# LPC1114_LedMatrix.net
KiCad netlist of a schematic drawn in EAGLE
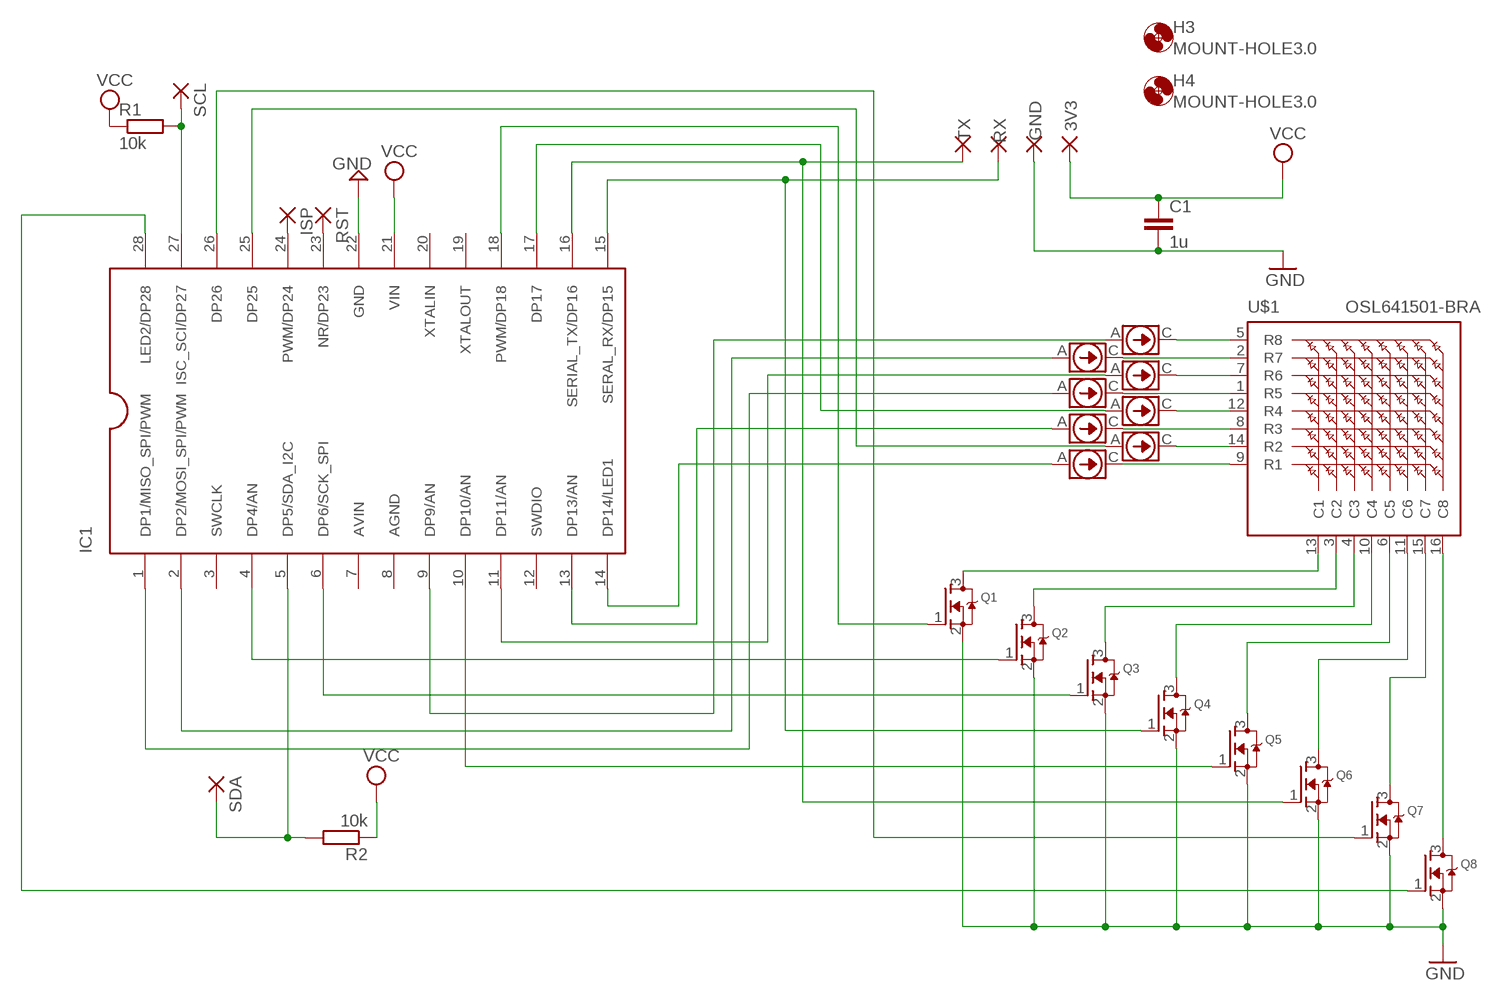
[diagram p0: schematic, sheet 1]

(export (version "E")
  (design (tool "Eeschema 10.0.6"))
  (components
    (comp (ref "3V3")
      (value "1,6/0,8")
      (footprint "eagle-import:1,6_0,8")
      (libsource (lib "eagle-import") (part "1,6/0,8"))
    )
    (comp (ref "C1")
      (value "1u")
      (footprint "eagle-import:C0603")
      (libsource (lib "eagle-import") (part "C-EUC0603"))
    )
    (comp (ref "CRD1")
      (value "NSI45020AT1G")
      (footprint "eagle-import:SOD-123")
      (libsource (lib "eagle-import") (part "NSI45020AT1G"))
    )
    (comp (ref "CRD2")
      (value "NSI45020AT1G")
      (footprint "eagle-import:SOD-123")
      (libsource (lib "eagle-import") (part "NSI45020AT1G"))
    )
    (comp (ref "CRD3")
      (value "NSI45020AT1G")
      (footprint "eagle-import:SOD-123")
      (libsource (lib "eagle-import") (part "NSI45020AT1G"))
    )
    (comp (ref "CRD4")
      (value "NSI45020AT1G")
      (footprint "eagle-import:SOD-123")
      (libsource (lib "eagle-import") (part "NSI45020AT1G"))
    )
    (comp (ref "CRD5")
      (value "NSI45020AT1G")
      (footprint "eagle-import:SOD-123")
      (libsource (lib "eagle-import") (part "NSI45020AT1G"))
    )
    (comp (ref "CRD6")
      (value "NSI45020AT1G")
      (footprint "eagle-import:SOD-123")
      (libsource (lib "eagle-import") (part "NSI45020AT1G"))
    )
    (comp (ref "CRD7")
      (value "NSI45020AT1G")
      (footprint "eagle-import:SOD-123")
      (libsource (lib "eagle-import") (part "NSI45020AT1G"))
    )
    (comp (ref "CRD8")
      (value "NSI45020AT1G")
      (footprint "eagle-import:SOD-123")
      (libsource (lib "eagle-import") (part "NSI45020AT1G"))
    )
    (comp (ref "GND")
      (value "1,6/0,8")
      (footprint "eagle-import:1,6_0,8")
      (libsource (lib "eagle-import") (part "1,6/0,8"))
    )
    (comp (ref "H3")
      (value "MOUNT-HOLE3.0")
      (footprint "eagle-import:3,0")
      (libsource (lib "eagle-import") (part "MOUNT-HOLE3.0"))
    )
    (comp (ref "H4")
      (value "MOUNT-HOLE3.0")
      (footprint "eagle-import:3,0")
      (libsource (lib "eagle-import") (part "MOUNT-HOLE3.0"))
    )
    (comp (ref "IC1")
      (value "LPC1114FN28")
      (footprint "eagle-import:DIP28")
      (libsource (lib "eagle-import") (part "LPC1114FN28"))
    )
    (comp (ref "ISP")
      (value "1,6/0,8")
      (footprint "eagle-import:1,6_0,8")
      (libsource (lib "eagle-import") (part "1,6/0,8"))
    )
    (comp (ref "Q1")
      (value "MOSFET-NREFLOW")
      (footprint "eagle-import:SOT23")
      (libsource (lib "eagle-import") (part "MOSFET-NREFLOW"))
    )
    (comp (ref "Q2")
      (value "MOSFET-NREFLOW")
      (footprint "eagle-import:SOT23")
      (libsource (lib "eagle-import") (part "MOSFET-NREFLOW"))
    )
    (comp (ref "Q3")
      (value "MOSFET-NREFLOW")
      (footprint "eagle-import:SOT23")
      (libsource (lib "eagle-import") (part "MOSFET-NREFLOW"))
    )
    (comp (ref "Q4")
      (value "MOSFET-NREFLOW")
      (footprint "eagle-import:SOT23")
      (libsource (lib "eagle-import") (part "MOSFET-NREFLOW"))
    )
    (comp (ref "Q5")
      (value "MOSFET-NREFLOW")
      (footprint "eagle-import:SOT23")
      (libsource (lib "eagle-import") (part "MOSFET-NREFLOW"))
    )
    (comp (ref "Q6")
      (value "MOSFET-NREFLOW")
      (footprint "eagle-import:SOT23")
      (libsource (lib "eagle-import") (part "MOSFET-NREFLOW"))
    )
    (comp (ref "Q7")
      (value "MOSFET-NREFLOW")
      (footprint "eagle-import:SOT23")
      (libsource (lib "eagle-import") (part "MOSFET-NREFLOW"))
    )
    (comp (ref "Q8")
      (value "MOSFET-NREFLOW")
      (footprint "eagle-import:SOT23")
      (libsource (lib "eagle-import") (part "MOSFET-NREFLOW"))
    )
    (comp (ref "R1")
      (value "10k")
      (footprint "eagle-import:R0603")
      (libsource (lib "eagle-import") (part "R-EU_R0603"))
    )
    (comp (ref "R2")
      (value "10k")
      (footprint "eagle-import:R0603")
      (libsource (lib "eagle-import") (part "R-EU_R0603"))
    )
    (comp (ref "RST")
      (value "1,6/0,8")
      (footprint "eagle-import:1,6_0,8")
      (libsource (lib "eagle-import") (part "1,6/0,8"))
    )
    (comp (ref "RX")
      (value "1,6/0,8")
      (footprint "eagle-import:1,6_0,8")
      (libsource (lib "eagle-import") (part "1,6/0,8"))
    )
    (comp (ref "SCL")
      (value "1,6/0,8")
      (footprint "eagle-import:1,6_0,8")
      (libsource (lib "eagle-import") (part "1,6/0,8"))
    )
    (comp (ref "SDA")
      (value "1,6/0,8")
      (footprint "eagle-import:1,6_0,8")
      (libsource (lib "eagle-import") (part "1,6/0,8"))
    )
    (comp (ref "TX")
      (value "1,6/0,8")
      (footprint "eagle-import:1,6_0,8")
      (libsource (lib "eagle-import") (part "1,6/0,8"))
    )
    (comp (ref "U$1")
      (value "OSL641501-BRA")
      (footprint "eagle-import:OSL641501")
      (libsource (lib "eagle-import") (part "OSL641501-BRA"))
    )
  )
  (nets
    (net (code "1") (name "/AGND") (class "Default")
      (node (ref "IC1") (pin "8") (pinfunction "AGND_8") (pintype "power_in"))
    )
    (net (code "2") (name "/AVIN") (class "Default")
      (node (ref "IC1") (pin "7") (pinfunction "AVIN_7") (pintype "power_in"))
    )
    (net (code "3") (name "GND") (class "Default")
      (node (ref "C1") (pin "2") (pinfunction "2_2") (pintype "passive"))
      (node (ref "GND") (pin "1") (pinfunction "P_1") (pintype "passive"))
      (node (ref "IC1") (pin "22") (pinfunction "GND_22") (pintype "power_in"))
      (node (ref "Q1") (pin "2") (pinfunction "S_2") (pintype "bidirectional"))
      (node (ref "Q2") (pin "2") (pinfunction "S_2") (pintype "bidirectional"))
      (node (ref "Q3") (pin "2") (pinfunction "S_2") (pintype "bidirectional"))
      (node (ref "Q4") (pin "2") (pinfunction "S_2") (pintype "bidirectional"))
      (node (ref "Q5") (pin "2") (pinfunction "S_2") (pintype "bidirectional"))
      (node (ref "Q6") (pin "2") (pinfunction "S_2") (pintype "bidirectional"))
      (node (ref "Q7") (pin "2") (pinfunction "S_2") (pintype "bidirectional"))
      (node (ref "Q8") (pin "2") (pinfunction "S_2") (pintype "bidirectional"))
    )
    (net (code "4") (name "Net-(CRD1-P$1)") (class "Default")
      (node (ref "CRD1") (pin "A") (pinfunction "P$1_A") (pintype "input"))
      (node (ref "IC1") (pin "14") (pinfunction "DP14/LED1_14") (pintype "bidirectional"))
    )
    (net (code "5") (name "Net-(CRD1-P$2)") (class "Default")
      (node (ref "CRD1") (pin "C") (pinfunction "P$2_C") (pintype "output"))
      (node (ref "U$1") (pin "9") (pinfunction "R1_9") (pintype "passive"))
    )
    (net (code "6") (name "Net-(CRD2-P$1)") (class "Default")
      (node (ref "CRD2") (pin "A") (pinfunction "P$1_A") (pintype "input"))
      (node (ref "IC1") (pin "25") (pinfunction "DP25_25") (pintype "bidirectional"))
    )
    (net (code "7") (name "Net-(CRD2-P$2)") (class "Default")
      (node (ref "CRD2") (pin "C") (pinfunction "P$2_C") (pintype "output"))
      (node (ref "U$1") (pin "14") (pinfunction "R2_14") (pintype "passive"))
    )
    (net (code "8") (name "Net-(CRD3-P$1)") (class "Default")
      (node (ref "CRD3") (pin "A") (pinfunction "P$1_A") (pintype "input"))
      (node (ref "IC1") (pin "13") (pinfunction "DP13/AN_13") (pintype "bidirectional"))
    )
    (net (code "9") (name "Net-(CRD3-P$2)") (class "Default")
      (node (ref "CRD3") (pin "C") (pinfunction "P$2_C") (pintype "output"))
      (node (ref "U$1") (pin "8") (pinfunction "R3_8") (pintype "passive"))
    )
    (net (code "10") (name "Net-(CRD4-P$1)") (class "Default")
      (node (ref "CRD4") (pin "A") (pinfunction "P$1_A") (pintype "input"))
      (node (ref "IC1") (pin "17") (pinfunction "DP17_17") (pintype "bidirectional"))
    )
    (net (code "11") (name "Net-(CRD4-P$2)") (class "Default")
      (node (ref "CRD4") (pin "C") (pinfunction "P$2_C") (pintype "output"))
      (node (ref "U$1") (pin "12") (pinfunction "R4_12") (pintype "passive"))
    )
    (net (code "12") (name "Net-(CRD5-P$1)") (class "Default")
      (node (ref "CRD5") (pin "A") (pinfunction "P$1_A") (pintype "input"))
      (node (ref "IC1") (pin "1") (pinfunction "DP1/MISO_SPI/PWM_1") (pintype "bidirectional"))
    )
    (net (code "13") (name "Net-(CRD5-P$2)") (class "Default")
      (node (ref "CRD5") (pin "C") (pinfunction "P$2_C") (pintype "output"))
      (node (ref "U$1") (pin "1") (pinfunction "R5_1") (pintype "passive"))
    )
    (net (code "14") (name "Net-(CRD6-P$1)") (class "Default")
      (node (ref "CRD6") (pin "A") (pinfunction "P$1_A") (pintype "input"))
      (node (ref "IC1") (pin "11") (pinfunction "DP11/AN_11") (pintype "bidirectional"))
    )
    (net (code "15") (name "Net-(CRD6-P$2)") (class "Default")
      (node (ref "CRD6") (pin "C") (pinfunction "P$2_C") (pintype "output"))
      (node (ref "U$1") (pin "7") (pinfunction "R6_7") (pintype "passive"))
    )
    (net (code "16") (name "Net-(CRD7-P$1)") (class "Default")
      (node (ref "CRD7") (pin "A") (pinfunction "P$1_A") (pintype "input"))
      (node (ref "IC1") (pin "2") (pinfunction "DP2/MOSI_SPI/PWM_2") (pintype "bidirectional"))
    )
    (net (code "17") (name "Net-(CRD7-P$2)") (class "Default")
      (node (ref "CRD7") (pin "C") (pinfunction "P$2_C") (pintype "output"))
      (node (ref "U$1") (pin "2") (pinfunction "R7_2") (pintype "passive"))
    )
    (net (code "18") (name "Net-(CRD8-P$1)") (class "Default")
      (node (ref "CRD8") (pin "A") (pinfunction "P$1_A") (pintype "input"))
      (node (ref "IC1") (pin "9") (pinfunction "DP9/AN_9") (pintype "bidirectional"))
    )
    (net (code "19") (name "Net-(CRD8-P$2)") (class "Default")
      (node (ref "CRD8") (pin "C") (pinfunction "P$2_C") (pintype "output"))
      (node (ref "U$1") (pin "5") (pinfunction "R8_5") (pintype "passive"))
    )
    (net (code "20") (name "Net-(IC1-DP4{slash}AN)") (class "Default")
      (node (ref "IC1") (pin "4") (pinfunction "DP4/AN_4") (pintype "bidirectional"))
      (node (ref "Q2") (pin "1") (pinfunction "G_1") (pintype "bidirectional"))
    )
    (net (code "21") (name "Net-(IC1-DP5{slash}SDA_I2C)") (class "Default")
      (node (ref "IC1") (pin "5") (pinfunction "DP5/SDA_I2C_5") (pintype "bidirectional"))
      (node (ref "R2") (pin "2") (pinfunction "2_2") (pintype "passive"))
      (node (ref "SDA") (pin "1") (pinfunction "P_1") (pintype "passive"))
    )
    (net (code "22") (name "Net-(IC1-DP6{slash}SCK_SPI)") (class "Default")
      (node (ref "IC1") (pin "6") (pinfunction "DP6/SCK_SPI_6") (pintype "bidirectional"))
      (node (ref "Q3") (pin "1") (pinfunction "G_1") (pintype "bidirectional"))
    )
    (net (code "23") (name "Net-(IC1-DP10{slash}AN)") (class "Default")
      (node (ref "IC1") (pin "10") (pinfunction "DP10/AN_10") (pintype "bidirectional"))
      (node (ref "Q5") (pin "1") (pinfunction "G_1") (pintype "bidirectional"))
    )
    (net (code "24") (name "Net-(IC1-DP26)") (class "Default")
      (node (ref "IC1") (pin "26") (pinfunction "DP26_26") (pintype "bidirectional"))
      (node (ref "Q7") (pin "1") (pinfunction "G_1") (pintype "bidirectional"))
    )
    (net (code "25") (name "Net-(IC1-ISC_SCI{slash}DP27)") (class "Default")
      (node (ref "IC1") (pin "27") (pinfunction "ISC_SCI/DP27_27") (pintype "bidirectional"))
      (node (ref "R1") (pin "2") (pinfunction "2_2") (pintype "passive"))
      (node (ref "SCL") (pin "1") (pinfunction "P_1") (pintype "passive"))
    )
    (net (code "26") (name "Net-(IC1-LED2{slash}DP28)") (class "Default")
      (node (ref "IC1") (pin "28") (pinfunction "LED2/DP28_28") (pintype "bidirectional"))
      (node (ref "Q8") (pin "1") (pinfunction "G_1") (pintype "bidirectional"))
    )
    (net (code "27") (name "Net-(IC1-NR{slash}DP23)") (class "Default")
      (node (ref "IC1") (pin "23") (pinfunction "NR/DP23_23") (pintype "bidirectional"))
      (node (ref "RST") (pin "1") (pinfunction "P_1") (pintype "passive"))
    )
    (net (code "28") (name "Net-(IC1-PWM{slash}DP18)") (class "Default")
      (node (ref "IC1") (pin "18") (pinfunction "PWM/DP18_18") (pintype "bidirectional"))
      (node (ref "Q1") (pin "1") (pinfunction "G_1") (pintype "bidirectional"))
    )
    (net (code "29") (name "Net-(IC1-PWM{slash}DP24)") (class "Default")
      (node (ref "IC1") (pin "24") (pinfunction "PWM/DP24_24") (pintype "bidirectional"))
      (node (ref "ISP") (pin "1") (pinfunction "P_1") (pintype "passive"))
    )
    (net (code "30") (name "Net-(IC1-SERAL_RX{slash}DP15)") (class "Default")
      (node (ref "IC1") (pin "15") (pinfunction "SERAL_RX/DP15_15") (pintype "bidirectional"))
      (node (ref "Q4") (pin "1") (pinfunction "G_1") (pintype "bidirectional"))
      (node (ref "RX") (pin "1") (pinfunction "P_1") (pintype "passive"))
    )
    (net (code "31") (name "Net-(IC1-SERIAL_TX{slash}DP16)") (class "Default")
      (node (ref "IC1") (pin "16") (pinfunction "SERIAL_TX/DP16_16") (pintype "bidirectional"))
      (node (ref "Q6") (pin "1") (pinfunction "G_1") (pintype "bidirectional"))
      (node (ref "TX") (pin "1") (pinfunction "P_1") (pintype "passive"))
    )
    (net (code "32") (name "Net-(Q1-D)") (class "Default")
      (node (ref "Q1") (pin "3") (pinfunction "D_3") (pintype "bidirectional"))
      (node (ref "U$1") (pin "13") (pinfunction "C1_13") (pintype "passive"))
    )
    (net (code "33") (name "Net-(Q2-D)") (class "Default")
      (node (ref "Q2") (pin "3") (pinfunction "D_3") (pintype "bidirectional"))
      (node (ref "U$1") (pin "3") (pinfunction "C2_3") (pintype "passive"))
    )
    (net (code "34") (name "Net-(Q3-D)") (class "Default")
      (node (ref "Q3") (pin "3") (pinfunction "D_3") (pintype "bidirectional"))
      (node (ref "U$1") (pin "4") (pinfunction "C3_4") (pintype "passive"))
    )
    (net (code "35") (name "Net-(Q4-D)") (class "Default")
      (node (ref "Q4") (pin "3") (pinfunction "D_3") (pintype "bidirectional"))
      (node (ref "U$1") (pin "10") (pinfunction "C4_10") (pintype "passive"))
    )
    (net (code "36") (name "Net-(Q5-D)") (class "Default")
      (node (ref "Q5") (pin "3") (pinfunction "D_3") (pintype "bidirectional"))
      (node (ref "U$1") (pin "6") (pinfunction "C5_6") (pintype "passive"))
    )
    (net (code "37") (name "Net-(Q6-D)") (class "Default")
      (node (ref "Q6") (pin "3") (pinfunction "D_3") (pintype "bidirectional"))
      (node (ref "U$1") (pin "11") (pinfunction "C6_11") (pintype "passive"))
    )
    (net (code "38") (name "Net-(Q7-D)") (class "Default")
      (node (ref "Q7") (pin "3") (pinfunction "D_3") (pintype "bidirectional"))
      (node (ref "U$1") (pin "15") (pinfunction "C7_15") (pintype "passive"))
    )
    (net (code "39") (name "Net-(Q8-D)") (class "Default")
      (node (ref "Q8") (pin "3") (pinfunction "D_3") (pintype "bidirectional"))
      (node (ref "U$1") (pin "16") (pinfunction "C8_16") (pintype "passive"))
    )
    (net (code "40") (name "VCC") (class "Default")
      (node (ref "3V3") (pin "1") (pinfunction "P_1") (pintype "passive"))
      (node (ref "C1") (pin "1") (pinfunction "1_1") (pintype "passive"))
      (node (ref "IC1") (pin "21") (pinfunction "VIN_21") (pintype "power_in"))
      (node (ref "R1") (pin "1") (pinfunction "1_1") (pintype "passive"))
      (node (ref "R2") (pin "1") (pinfunction "1_1") (pintype "passive"))
    )
    (net (code "41") (name "unconnected-(IC1-SWCLK-Pad3)") (class "Default")
      (node (ref "IC1") (pin "3") (pinfunction "SWCLK_3") (pintype "bidirectional"))
    )
    (net (code "42") (name "unconnected-(IC1-SWDIO-Pad12)") (class "Default")
      (node (ref "IC1") (pin "12") (pinfunction "SWDIO_12") (pintype "bidirectional"))
    )
    (net (code "43") (name "unconnected-(IC1-XTALIN-Pad20)") (class "Default")
      (node (ref "IC1") (pin "20") (pinfunction "XTALIN_20") (pintype "input"))
    )
    (net (code "44") (name "unconnected-(IC1-XTALOUT-Pad19)") (class "Default")
      (node (ref "IC1") (pin "19") (pinfunction "XTALOUT_19") (pintype "output"))
    )
  )
)
